# Potions_Cabinet.net
KiCad netlist of a schematic drawn in EAGLE
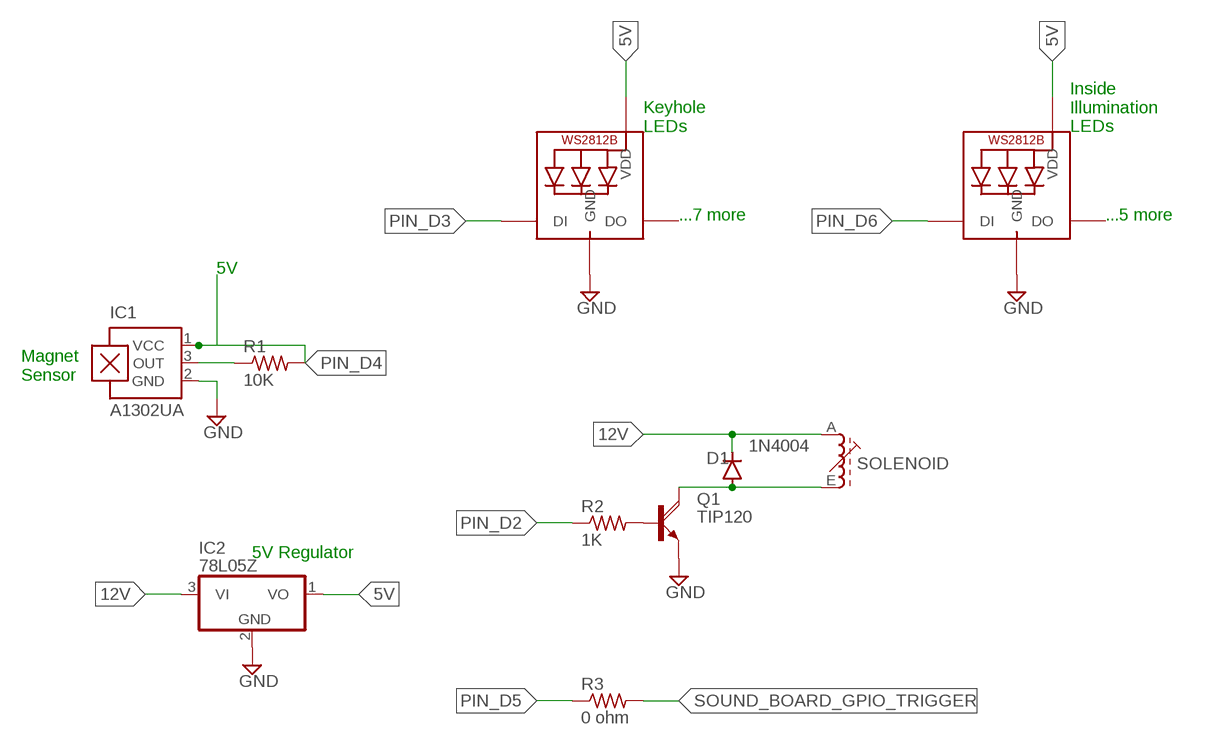
[diagram p0: schematic, sheet 1]

(export (version "E")
  (design (tool "Eeschema 10.0.6"))
  (components
    (comp (ref "D1")
      (value "1N4004")
      (footprint "eagle-import:DO41-10")
      (libsource (lib "eagle-import") (part "1N4004"))
    )
    (comp (ref "IC1")
      (value "A1302UA")
      (footprint "eagle-import:SIP3-UA")
      (fields (field (name "MF") "ALLEGRO MICROSYSTEMS, INC.") (field (name "MPN") "A1302EUA-T"))
      (libsource (lib "eagle-import") (part "A13?UA02"))
    )
    (comp (ref "IC2")
      (value "78L05Z")
      (footprint "eagle-import:TO92")
      (libsource (lib "eagle-import") (part "78ZL05"))
    )
    (comp (ref "LED1")
      (value "WS2812B3535")
      (footprint "eagle-import:LED3535")
      (libsource (lib "eagle-import") (part "WS2812B3535"))
    )
    (comp (ref "LED2")
      (value "WS2812B3535")
      (footprint "eagle-import:LED3535")
      (libsource (lib "eagle-import") (part "WS2812B3535"))
    )
    (comp (ref "Q1")
      (value "TIP120")
      (footprint "eagle-import:TO220AH")
      (libsource (lib "eagle-import") (part "TIP120"))
    )
    (comp (ref "R1")
      (value "10K")
      (footprint "eagle-import:0204_7")
      (libsource (lib "eagle-import") (part "R-US_0204/7"))
    )
    (comp (ref "R2")
      (value "1K")
      (footprint "eagle-import:0204_7")
      (libsource (lib "eagle-import") (part "R-US_0204/7"))
    )
    (comp (ref "R3")
      (value "0 ohm")
      (footprint "eagle-import:0204_7")
      (libsource (lib "eagle-import") (part "R-US_0204/7"))
    )
    (comp (ref "SOLENOID")
      (value "71E")
      (footprint "eagle-import:71E")
      (libsource (lib "eagle-import") (part "71E"))
    )
  )
  (nets
    (net (code "1") (name "5V") (class "Default")
      (node (ref "IC2") (pin "1") (pinfunction "VO_1") (pintype "passive"))
      (node (ref "LED1") (pin "2") (pinfunction "VDD_2") (pintype "power_in"))
      (node (ref "LED2") (pin "2") (pinfunction "VDD_2") (pintype "power_in"))
    )
    (net (code "2") (name "12V") (class "Default")
      (node (ref "D1") (pin "C") (pinfunction "C_C") (pintype "passive"))
      (node (ref "IC2") (pin "3") (pinfunction "VI_3") (pintype "input"))
      (node (ref "SOLENOID") (pin "A") (pinfunction "A_A") (pintype "passive"))
    )
    (net (code "3") (name "GND") (class "Default")
      (node (ref "IC1") (pin "2") (pinfunction "GND_2") (pintype "power_in"))
      (node (ref "IC2") (pin "2") (pinfunction "GND_2") (pintype "passive"))
      (node (ref "LED1") (pin "4") (pinfunction "GND_4") (pintype "power_in"))
      (node (ref "LED2") (pin "4") (pinfunction "GND_4") (pintype "power_in"))
      (node (ref "Q1") (pin "E") (pinfunction "E_E") (pintype "passive"))
    )
    (net (code "4") (name "Net-(D1-PadA)") (class "Default")
      (node (ref "D1") (pin "A") (pinfunction "A_A") (pintype "passive"))
      (node (ref "Q1") (pin "C") (pinfunction "C_C") (pintype "passive"))
      (node (ref "SOLENOID") (pin "E") (pinfunction "E_E") (pintype "passive"))
    )
    (net (code "5") (name "Net-(IC1-OUT)") (class "Default")
      (node (ref "IC1") (pin "3") (pinfunction "OUT_3") (pintype "output"))
      (node (ref "R1") (pin "1") (pinfunction "1_1") (pintype "passive"))
    )
    (net (code "6") (name "Net-(Q1-PadB)") (class "Default")
      (node (ref "Q1") (pin "B") (pinfunction "B_B") (pintype "passive"))
      (node (ref "R2") (pin "2") (pinfunction "2_2") (pintype "passive"))
    )
    (net (code "7") (name "PIN_D2") (class "Default")
      (node (ref "R2") (pin "1") (pinfunction "1_1") (pintype "passive"))
    )
    (net (code "8") (name "PIN_D3") (class "Default")
      (node (ref "LED1") (pin "1") (pinfunction "DI_1") (pintype "input"))
    )
    (net (code "9") (name "PIN_D4") (class "Default")
      (node (ref "IC1") (pin "1") (pinfunction "VCC_1") (pintype "power_in"))
      (node (ref "R1") (pin "2") (pinfunction "2_2") (pintype "passive"))
    )
    (net (code "10") (name "PIN_D5") (class "Default")
      (node (ref "R3") (pin "1") (pinfunction "1_1") (pintype "passive"))
    )
    (net (code "11") (name "PIN_D6") (class "Default")
      (node (ref "LED2") (pin "1") (pinfunction "DI_1") (pintype "input"))
    )
    (net (code "12") (name "SOUND_BOARD_GPIO_TRIGGER") (class "Default")
      (node (ref "R3") (pin "2") (pinfunction "2_2") (pintype "passive"))
    )
    (net (code "13") (name "unconnected-(LED1-DO-Pad3)") (class "Default")
      (node (ref "LED1") (pin "3") (pinfunction "DO_3") (pintype "output"))
    )
    (net (code "14") (name "unconnected-(LED2-DO-Pad3)") (class "Default")
      (node (ref "LED2") (pin "3") (pinfunction "DO_3") (pintype "output"))
    )
  )
)
